# RMII.net
KiCad netlist of a schematic drawn in Altium Designer
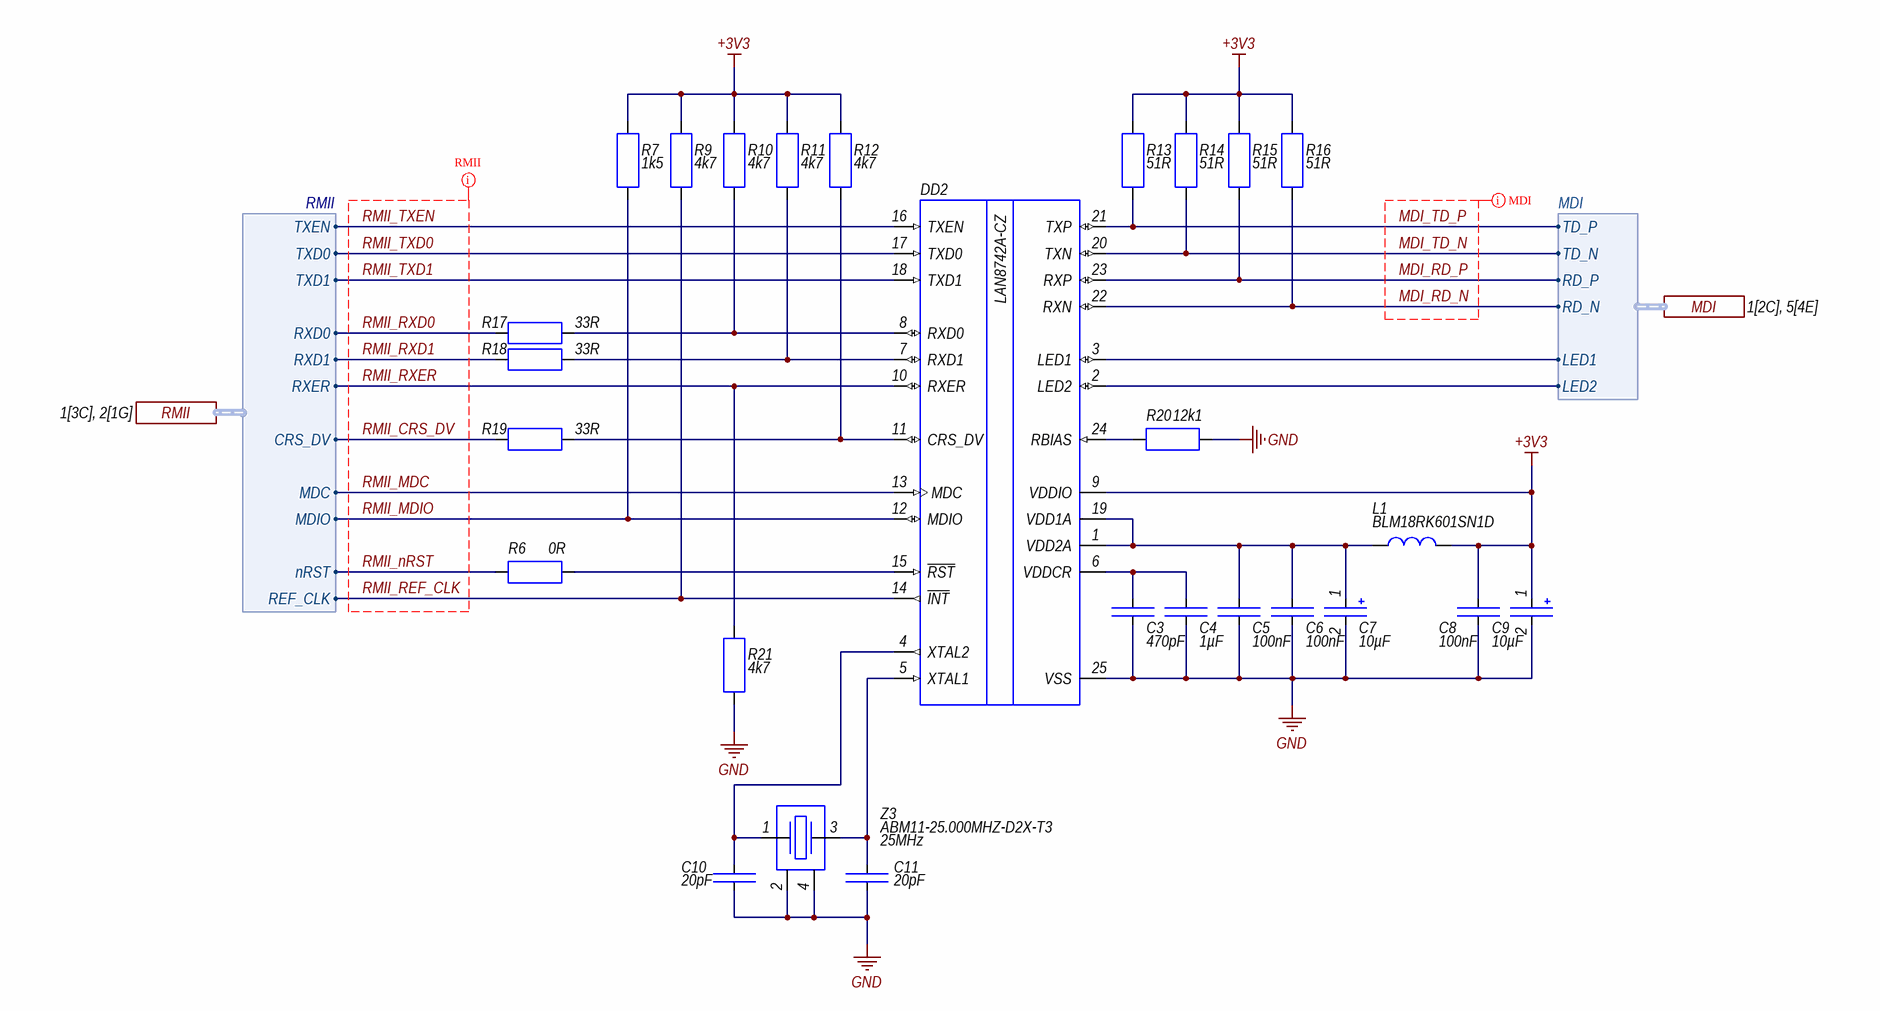
[diagram p0: RMII.SchDoc]

(export (version "E")
  (design (tool "Eeschema 10.0.6"))
  (components
    (comp (ref "C3")
      (value "Конденсатор керам. ЧИП Х7R, 5%, 0603, 470 пФ")
      (footprint "Capacitor 0603")
      (fields
        (field (name "CAPACITANCE") "470pF")
        (field (name "VOLTAGE") "50V")
        (field (name "MANUFACTURER") "Kemet Electronics")
        (field (name "MANUFACTURER PART NUMBER") "C0603C471J5RACTU")
      )
      (libsource (lib "Eleps server") (part "Nonpolar Capacitor"))
    )
    (comp (ref "C4")
      (value "Конденсатор керам. ЧИП X5R, 10%, 0603, 1 мкФ")
      (footprint "Capacitor 0603")
      (description "Multilayer Ceramic Capacitors MLCC - SMD/SMT 0603 50V 1.0uF X5R 10%")
      (fields
        (field (name "CAPACITANCE") "1µF")
        (field (name "VOLTAGE") "50V")
        (field (name "MANUFACTURER") "Murata Electronics")
      )
      (libsource (lib "Eleps server") (part "Nonpolar Capacitor"))
    )
    (comp (ref "C5")
      (value "Конденсатор керам. ЧИП X7R, 10%, 0603, 0.1 мкФ")
      (footprint "Capacitor 0603")
      (fields
        (field (name "DEVICE") "100nF")
        (field (name "VOLTAGE") "50V")
        (field (name "MANUFACTURER") "Yageo")
        (field (name "MANUFACTURER PART NUMBER") "CC0603KPX7R9BB104")
      )
      (libsource (lib "Eleps server") (part "Nonpolar Capacitor"))
    )
    (comp (ref "C6")
      (value "Конденсатор керам. ЧИП X7R, 10%, 0603, 0.1 мкФ")
      (footprint "Capacitor 0603")
      (fields
        (field (name "DEVICE") "100nF")
        (field (name "VOLTAGE") "50V")
        (field (name "MANUFACTURER") "Yageo")
        (field (name "MANUFACTURER PART NUMBER") "CC0603KPX7R9BB104")
      )
      (libsource (lib "Eleps server") (part "Nonpolar Capacitor"))
    )
    (comp (ref "C7")
      (value "Конденсатор тантал. ЧИП 10мкФ х 16 В тип A (AА7)")
      (footprint "SMD TANTAL-A")
      (fields (field (name "DEVICE") "10µF") (field (name "VOLTAGE") "16V"))
      (libsource (lib "Eleps server") (part "PolarCap_P1N2"))
    )
    (comp (ref "C8")
      (value "Конденсатор керам. ЧИП X7R, 10%, 0603, 0.1 мкФ")
      (footprint "Capacitor 0603")
      (fields
        (field (name "DEVICE") "100nF")
        (field (name "VOLTAGE") "50V")
        (field (name "MANUFACTURER") "Yageo")
        (field (name "MANUFACTURER PART NUMBER") "CC0603KPX7R9BB104")
      )
      (libsource (lib "Eleps server") (part "Nonpolar Capacitor"))
    )
    (comp (ref "C9")
      (value "Конденсатор тантал. ЧИП 10мкФ х 16 В тип A (AА7)")
      (footprint "SMD TANTAL-A")
      (fields (field (name "DEVICE") "10µF") (field (name "VOLTAGE") "16V"))
      (libsource (lib "Eleps server") (part "PolarCap_P1N2"))
    )
    (comp (ref "C10")
      (value "Конденсатор керам. ЧИП NPO, 5%, 0603, 20 пФ")
      (footprint "Capacitor 0603")
      (fields
        (field (name "CAPACITANCE") "20pF")
        (field (name "VOLTAGE") "50V")
        (field (name "MANUFACTURER") "Murata Manufacturing")
        (field (name "MANUFACTURER PART NUMBER") "GRM1885C1H200J")
      )
      (libsource (lib "Eleps server") (part "Nonpolar Capacitor"))
    )
    (comp (ref "C11")
      (value "Конденсатор керам. ЧИП NPO, 5%, 0603, 20 пФ")
      (footprint "Capacitor 0603")
      (fields
        (field (name "CAPACITANCE") "20pF")
        (field (name "VOLTAGE") "50V")
        (field (name "MANUFACTURER") "Murata Manufacturing")
        (field (name "MANUFACTURER PART NUMBER") "GRM1885C1H200J")
      )
      (libsource (lib "Eleps server") (part "Nonpolar Capacitor"))
    )
    (comp (ref "DD2")
      (value "Микросхема LAN8742A-CZ")
      (footprint "FP-C04-143B-S4QFN-MFG")
      (description "Small Footprint RMII 10/100 Ethernet Transceiver with HP Auto-MDIX and flexPWR Technology")
      (fields
        (field (name "MANUFACTURER") "Microchip")
        (field (name "MANUFACTURER PART NUMBER") "LAN8742A-CZ")
        (field (name "DEVICE") "LAN8742A-CZ")
      )
      (libsource (lib "Eleps server") (part "LAN8742A-CZ"))
    )
    (comp (ref "L1")
      (value "Дроссель BLM18RK601SN1D")
      (footprint "BLM18HE152SN1D")
      (description "Ferrite Beads Multi-Layer 600Ohm 25% 100MHz 200mA 600mOhm DCR 0603 T/R")
      (fields
        (field (name "MANUFACTURER") "Murata Electronics")
        (field (name "MANUFACTURER PART NUMBER") "BLM18RK601SN1D")
      )
      (libsource (lib "Concord Pro") (part "Inductor"))
    )
    (comp (ref "R6")
      (value "Resistor")
      (footprint "SMD_0402")
      (fields (field (name "DEVICE") "0R") (field (name "PART NUMBER") "Resistor_0402"))
      (libsource (lib "") (part "Resistor_1"))
    )
    (comp (ref "R7")
      (value "Resistor")
      (footprint "SMD_0402")
      (fields (field (name "DEVICE") "1k5") (field (name "PART NUMBER") "Resistor_0402"))
      (libsource (lib "PhLib") (part "Resistor"))
    )
    (comp (ref "R9")
      (value "Resistor")
      (footprint "SMD_0402")
      (fields (field (name "DEVICE") "4k7") (field (name "PART NUMBER") "Resistor_0402"))
      (libsource (lib "PhLib") (part "Resistor"))
    )
    (comp (ref "R10")
      (value "Resistor")
      (footprint "SMD_0402")
      (fields (field (name "DEVICE") "4k7") (field (name "PART NUMBER") "Resistor_0402"))
      (libsource (lib "PhLib") (part "Resistor"))
    )
    (comp (ref "R11")
      (value "Resistor")
      (footprint "SMD_0402")
      (fields (field (name "DEVICE") "4k7") (field (name "PART NUMBER") "Resistor_0402"))
      (libsource (lib "PhLib") (part "Resistor"))
    )
    (comp (ref "R12")
      (value "Resistor")
      (footprint "SMD_0402")
      (fields (field (name "DEVICE") "4k7") (field (name "PART NUMBER") "Resistor_0402"))
      (libsource (lib "PhLib") (part "Resistor"))
    )
    (comp (ref "R13")
      (value "Resistor")
      (footprint "SMD_0402")
      (fields (field (name "DEVICE") "51R") (field (name "PART NUMBER") "Resistor_0402"))
      (libsource (lib "PhLib") (part "Resistor"))
    )
    (comp (ref "R14")
      (value "Resistor")
      (footprint "SMD_0402")
      (fields (field (name "DEVICE") "51R") (field (name "PART NUMBER") "Resistor_0402"))
      (libsource (lib "PhLib") (part "Resistor"))
    )
    (comp (ref "R15")
      (value "Resistor")
      (footprint "SMD_0402")
      (fields (field (name "DEVICE") "51R") (field (name "PART NUMBER") "Resistor_0402"))
      (libsource (lib "PhLib") (part "Resistor"))
    )
    (comp (ref "R16")
      (value "Resistor")
      (footprint "SMD_0402")
      (fields (field (name "DEVICE") "51R") (field (name "PART NUMBER") "Resistor_0402"))
      (libsource (lib "PhLib") (part "Resistor"))
    )
    (comp (ref "R17")
      (value "Resistor")
      (footprint "SMD_0402")
      (fields (field (name "DEVICE") "33R") (field (name "PART NUMBER") "Resistor_0402"))
      (libsource (lib "") (part "Resistor_1"))
    )
    (comp (ref "R18")
      (value "Resistor")
      (footprint "SMD_0402")
      (fields (field (name "DEVICE") "33R") (field (name "PART NUMBER") "Resistor_0402"))
      (libsource (lib "") (part "Resistor_1"))
    )
    (comp (ref "R19")
      (value "Resistor")
      (footprint "SMD_0402")
      (fields (field (name "DEVICE") "33R") (field (name "PART NUMBER") "Resistor_0402"))
      (libsource (lib "") (part "Resistor_1"))
    )
    (comp (ref "R20")
      (value "Resistor")
      (footprint "SMD_0402")
      (fields (field (name "DEVICE") "12k1") (field (name "PART NUMBER") "Resistor_0402"))
      (libsource (lib "") (part "Resistor_1"))
    )
    (comp (ref "R21")
      (value "Resistor")
      (footprint "SMD_0402")
      (fields (field (name "DEVICE") "4k7") (field (name "PART NUMBER") "Resistor_0402"))
      (libsource (lib "PhLib") (part "Resistor"))
    )
    (comp (ref "Z3")
      (value "Резонатор ABM11-25.000MHZ-D2X-T3")
      (footprint "ABM11-MFG")
      (description "Crystal 25MHz ±20ppm (Tol) ±20ppm (Stability) 10pF FUND 100Ohm 4-Pin Ultra Mini-CSMD T/R")
      (fields
        (field (name "MANUFACTURER") "Abracon")
        (field (name "MANUFACTURER PART NUMBER") "ABM11-25.000MHZ-D2X-T3")
        (field (name "DEVICE") "25MHz")
      )
      (libsource (lib "Altium Vault") (part "KX-9A"))
    )
  )
  (nets
    (net (code "3") (name "+3V3") (class "Default")
      (node (ref "C8") (pin "1") (pinfunction "1_1") (pintype "passive"))
      (node (ref "C9") (pin "1") (pinfunction "1_1") (pintype "power_in"))
      (node (ref "DD2") (pin "9") (pinfunction "VDDIO_9") (pintype "power_in"))
      (node (ref "L1") (pin "2") (pinfunction "2_2") (pintype "passive"))
      (node (ref "R10") (pin "2") (pinfunction "2_2") (pintype "passive"))
      (node (ref "R11") (pin "2") (pinfunction "2_2") (pintype "passive"))
      (node (ref "R12") (pin "2") (pinfunction "2_2") (pintype "passive"))
      (node (ref "R13") (pin "2") (pinfunction "2_2") (pintype "passive"))
      (node (ref "R14") (pin "2") (pinfunction "2_2") (pintype "passive"))
      (node (ref "R15") (pin "2") (pinfunction "2_2") (pintype "passive"))
      (node (ref "R16") (pin "2") (pinfunction "2_2") (pintype "passive"))
      (node (ref "R7") (pin "2") (pinfunction "2_2") (pintype "passive"))
      (node (ref "R9") (pin "2") (pinfunction "2_2") (pintype "passive"))
    )
    (net (code "4") (name "/LED1") (class "Default")
      (node (ref "DD2") (pin "3") (pinfunction "LED1_3") (pintype "bidirectional"))
    )
    (net (code "5") (name "/LED2") (class "Default")
      (node (ref "DD2") (pin "2") (pinfunction "LED2_2") (pintype "bidirectional"))
    )
    (net (code "6") (name "/MDI_RD_N") (class "Default")
      (node (ref "DD2") (pin "22") (pinfunction "RXN_22") (pintype "bidirectional"))
      (node (ref "R16") (pin "1") (pinfunction "1_1") (pintype "passive"))
    )
    (net (code "7") (name "/MDI_RD_P") (class "Default")
      (node (ref "DD2") (pin "23") (pinfunction "RXP_23") (pintype "bidirectional"))
      (node (ref "R15") (pin "1") (pinfunction "1_1") (pintype "passive"))
    )
    (net (code "8") (name "/MDI_TD_N") (class "Default")
      (node (ref "DD2") (pin "20") (pinfunction "TXN_20") (pintype "bidirectional"))
      (node (ref "R14") (pin "1") (pinfunction "1_1") (pintype "passive"))
    )
    (net (code "9") (name "/MDI_TD_P") (class "Default")
      (node (ref "DD2") (pin "21") (pinfunction "TXP_21") (pintype "bidirectional"))
      (node (ref "R13") (pin "1") (pinfunction "1_1") (pintype "passive"))
    )
    (net (code "10") (name "/RMII_CRS_DV") (class "Default")
      (node (ref "R19") (pin "1") (pinfunction "1_1") (pintype "passive"))
    )
    (net (code "11") (name "/RMII_MDC") (class "Default")
      (node (ref "DD2") (pin "13") (pinfunction "MDC_13") (pintype "input"))
    )
    (net (code "12") (name "/RMII_MDIO") (class "Default")
      (node (ref "DD2") (pin "12") (pinfunction "MDIO_12") (pintype "bidirectional"))
      (node (ref "R7") (pin "1") (pinfunction "1_1") (pintype "passive"))
    )
    (net (code "13") (name "/RMII_REF_CLK") (class "Default")
      (node (ref "DD2") (pin "14") (pinfunction "~{INT}_14") (pintype "output"))
      (node (ref "R9") (pin "1") (pinfunction "1_1") (pintype "passive"))
    )
    (net (code "14") (name "/RMII_RXD0") (class "Default")
      (node (ref "R17") (pin "1") (pinfunction "1_1") (pintype "passive"))
    )
    (net (code "15") (name "/RMII_RXD1") (class "Default")
      (node (ref "R18") (pin "1") (pinfunction "1_1") (pintype "passive"))
    )
    (net (code "16") (name "/RMII_RXER") (class "Default")
      (node (ref "DD2") (pin "10") (pinfunction "RXER_10") (pintype "bidirectional"))
      (node (ref "R21") (pin "2") (pinfunction "2_2") (pintype "passive"))
    )
    (net (code "17") (name "/RMII_TXD0") (class "Default")
      (node (ref "DD2") (pin "17") (pinfunction "TXD0_17") (pintype "input"))
    )
    (net (code "18") (name "/RMII_TXD1") (class "Default")
      (node (ref "DD2") (pin "18") (pinfunction "TXD1_18") (pintype "input"))
    )
    (net (code "19") (name "/RMII_TXEN") (class "Default")
      (node (ref "DD2") (pin "16") (pinfunction "TXEN_16") (pintype "input"))
    )
    (net (code "20") (name "/RMII_nRST") (class "Default")
      (node (ref "R6") (pin "1") (pinfunction "1_1") (pintype "passive"))
    )
    (net (code "23") (name "GND") (class "Default")
      (node (ref "C10") (pin "2") (pinfunction "2_2") (pintype "passive"))
      (node (ref "C11") (pin "2") (pinfunction "2_2") (pintype "passive"))
      (node (ref "C3") (pin "2") (pinfunction "2_2") (pintype "passive"))
      (node (ref "C4") (pin "2") (pinfunction "2_2") (pintype "passive"))
      (node (ref "C5") (pin "2") (pinfunction "2_2") (pintype "passive"))
      (node (ref "C6") (pin "2") (pinfunction "2_2") (pintype "passive"))
      (node (ref "C7") (pin "2") (pinfunction "2_2") (pintype "power_in"))
      (node (ref "C8") (pin "2") (pinfunction "2_2") (pintype "passive"))
      (node (ref "C9") (pin "2") (pinfunction "2_2") (pintype "power_in"))
      (node (ref "DD2") (pin "25") (pinfunction "VSS_25") (pintype "power_in"))
      (node (ref "R20") (pin "2") (pinfunction "2_2") (pintype "passive"))
      (node (ref "R21") (pin "1") (pinfunction "1_1") (pintype "passive"))
      (node (ref "Z3") (pin "2") (pinfunction "2_2") (pintype "passive"))
      (node (ref "Z3") (pin "4") (pinfunction "4_4") (pintype "passive"))
    )
    (net (code "24") (name "Net-(DD2-CRS_DV)") (class "Default")
      (node (ref "DD2") (pin "11") (pinfunction "CRS_DV_11") (pintype "bidirectional"))
      (node (ref "R12") (pin "1") (pinfunction "1_1") (pintype "passive"))
      (node (ref "R19") (pin "2") (pinfunction "2_2") (pintype "passive"))
    )
    (net (code "25") (name "Net-(DD2-RBIAS)") (class "Default")
      (node (ref "DD2") (pin "24") (pinfunction "RBIAS_24") (pintype "input"))
      (node (ref "R20") (pin "1") (pinfunction "1_1") (pintype "passive"))
    )
    (net (code "26") (name "Net-(DD2-RXD0)") (class "Default")
      (node (ref "DD2") (pin "8") (pinfunction "RXD0_8") (pintype "bidirectional"))
      (node (ref "R10") (pin "1") (pinfunction "1_1") (pintype "passive"))
      (node (ref "R17") (pin "2") (pinfunction "2_2") (pintype "passive"))
    )
    (net (code "27") (name "Net-(DD2-RXD1)") (class "Default")
      (node (ref "DD2") (pin "7") (pinfunction "RXD1_7") (pintype "bidirectional"))
      (node (ref "R11") (pin "1") (pinfunction "1_1") (pintype "passive"))
      (node (ref "R18") (pin "2") (pinfunction "2_2") (pintype "passive"))
    )
    (net (code "28") (name "Net-(DD2-VDD1A)") (class "Default")
      (node (ref "C5") (pin "1") (pinfunction "1_1") (pintype "passive"))
      (node (ref "C6") (pin "1") (pinfunction "1_1") (pintype "passive"))
      (node (ref "C7") (pin "1") (pinfunction "1_1") (pintype "power_in"))
      (node (ref "DD2") (pin "1") (pinfunction "VDD2A_1") (pintype "power_in"))
      (node (ref "DD2") (pin "19") (pinfunction "VDD1A_19") (pintype "power_in"))
      (node (ref "L1") (pin "1") (pinfunction "1_1") (pintype "passive"))
    )
    (net (code "29") (name "Net-(DD2-VDDCR)") (class "Default")
      (node (ref "C3") (pin "1") (pinfunction "1_1") (pintype "passive"))
      (node (ref "C4") (pin "1") (pinfunction "1_1") (pintype "passive"))
      (node (ref "DD2") (pin "6") (pinfunction "VDDCR_6") (pintype "power_in"))
    )
    (net (code "30") (name "Net-(DD2-XTAL1)") (class "Default")
      (node (ref "C11") (pin "1") (pinfunction "1_1") (pintype "passive"))
      (node (ref "DD2") (pin "5") (pinfunction "XTAL1_5") (pintype "input"))
      (node (ref "Z3") (pin "3") (pinfunction "3_3") (pintype "passive"))
    )
    (net (code "31") (name "Net-(DD2-XTAL2)") (class "Default")
      (node (ref "C10") (pin "1") (pinfunction "1_1") (pintype "passive"))
      (node (ref "DD2") (pin "4") (pinfunction "XTAL2_4") (pintype "output"))
      (node (ref "Z3") (pin "1") (pinfunction "1_1") (pintype "passive"))
    )
    (net (code "32") (name "Net-(DD2-~{RST})") (class "Default")
      (node (ref "DD2") (pin "15") (pinfunction "~{RST}_15") (pintype "input"))
      (node (ref "R6") (pin "2") (pinfunction "2_2") (pintype "passive"))
    )
  )
)
